# Sheet1.net
KiCad netlist of a schematic drawn in Altium Designer
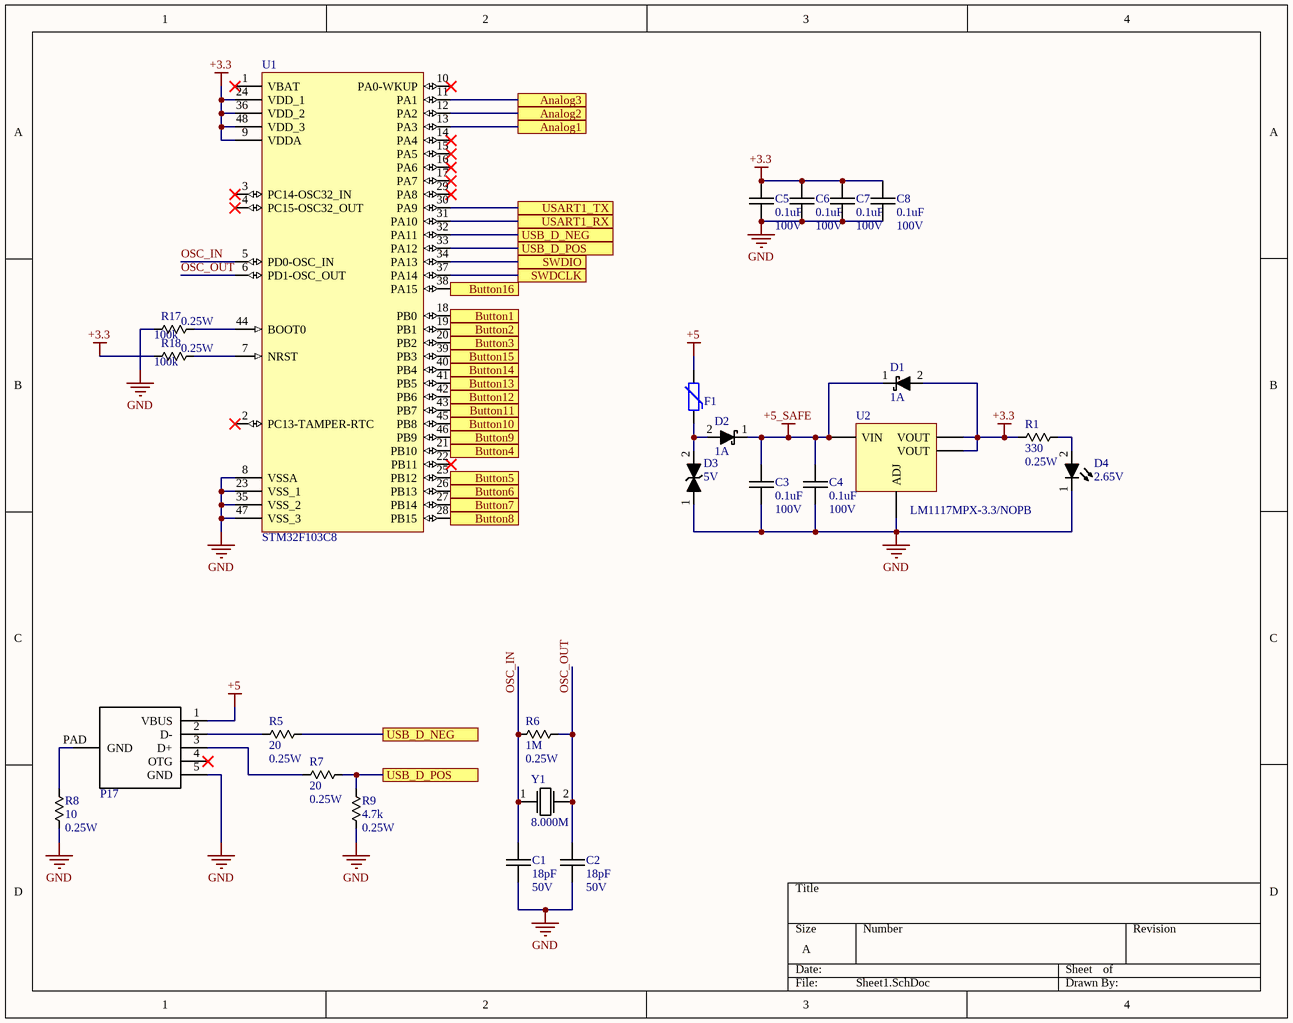
[diagram p0: Sheet1.SchDoc]

(export (version "E")
  (design (tool "Eeschema 10.0.6"))
  (components
    (comp (ref "C1")
      (value "cap_single_np")
      (footprint "chip_0603")
      (description "CAP, 18pF, ±2%, 50V, C0G, 0603")
      (fields
        (field (name "TOLERANCE") "±2%")
        (field (name "CAPACITANCE") "18pF")
        (field (name "VOLTAGE RATING") "50V")
        (field (name "PART NUMBER") "CAP-00409")
      )
      (libsource (lib "Capacitors") (part "cap_single_np"))
    )
    (comp (ref "C2")
      (value "cap_single_np")
      (footprint "chip_0603")
      (description "CAP, 18pF, ±2%, 50V, C0G, 0603")
      (fields
        (field (name "TOLERANCE") "±2%")
        (field (name "CAPACITANCE") "18pF")
        (field (name "VOLTAGE RATING") "50V")
        (field (name "PART NUMBER") "CAP-00409")
      )
      (libsource (lib "Capacitors") (part "cap_single_np"))
    )
    (comp (ref "C3")
      (value "cap_single_np")
      (footprint "chip_0603")
      (description "CAP, 0.1uF, ±10%, 100V, X7R, 0603")
      (fields
        (field (name "TOLERANCE") "±10%")
        (field (name "CAPACITANCE") "0.1uF")
        (field (name "VOLTAGE RATING") "100V")
        (field (name "PART NUMBER") "CAP-00477")
      )
      (libsource (lib "Capacitors") (part "cap_single_np"))
    )
    (comp (ref "C4")
      (value "cap_single_np")
      (footprint "chip_0603")
      (description "CAP, 0.1uF, ±10%, 100V, X7R, 0603")
      (fields
        (field (name "TOLERANCE") "±10%")
        (field (name "CAPACITANCE") "0.1uF")
        (field (name "VOLTAGE RATING") "100V")
        (field (name "PART NUMBER") "CAP-00477")
      )
      (libsource (lib "Capacitors") (part "cap_single_np"))
    )
    (comp (ref "C5")
      (value "cap_single_np")
      (footprint "chip_0603")
      (description "CAP, 0.1uF, ±10%, 100V, X7R, 0603")
      (fields
        (field (name "TOLERANCE") "±10%")
        (field (name "CAPACITANCE") "0.1uF")
        (field (name "VOLTAGE RATING") "100V")
        (field (name "PART NUMBER") "CAP-00477")
      )
      (libsource (lib "Capacitors") (part "cap_single_np"))
    )
    (comp (ref "C6")
      (value "cap_single_np")
      (footprint "chip_0603")
      (description "CAP, 0.1uF, ±10%, 100V, X7R, 0603")
      (fields
        (field (name "TOLERANCE") "±10%")
        (field (name "CAPACITANCE") "0.1uF")
        (field (name "VOLTAGE RATING") "100V")
        (field (name "PART NUMBER") "CAP-00477")
      )
      (libsource (lib "Capacitors") (part "cap_single_np"))
    )
    (comp (ref "C7")
      (value "cap_single_np")
      (footprint "chip_0603")
      (description "CAP, 0.1uF, ±10%, 100V, X7R, 0603")
      (fields
        (field (name "TOLERANCE") "±10%")
        (field (name "CAPACITANCE") "0.1uF")
        (field (name "VOLTAGE RATING") "100V")
        (field (name "PART NUMBER") "CAP-00477")
      )
      (libsource (lib "Capacitors") (part "cap_single_np"))
    )
    (comp (ref "C8")
      (value "cap_single_np")
      (footprint "chip_0603")
      (description "CAP, 0.1uF, ±10%, 100V, X7R, 0603")
      (fields
        (field (name "TOLERANCE") "±10%")
        (field (name "CAPACITANCE") "0.1uF")
        (field (name "VOLTAGE RATING") "100V")
        (field (name "PART NUMBER") "CAP-00477")
      )
      (libsource (lib "Capacitors") (part "cap_single_np"))
    )
    (comp (ref "D1")
      (value "diode_2")
      (footprint "sod123_0")
      (description "Dio Shtky, 1A, 0.55V, 40V, SOD-123")
      (fields
        (field (name "CURRENT RATING") "1A")
        (field (name "PART NUMBER") "DIO-00001")
        (field (name "MANUFACTURER") "ON Semi")
      )
      (libsource (lib "Diodes") (part "diode_2"))
    )
    (comp (ref "D2")
      (value "diode_2")
      (footprint "sod123_0")
      (description "Dio Shtky, 1A, 0.55V, 40V, SOD-123")
      (fields
        (field (name "CURRENT RATING") "1A")
        (field (name "PART NUMBER") "DIO-00001")
        (field (name "MANUFACTURER") "ON Semi")
      )
      (libsource (lib "Diodes") (part "diode_2"))
    )
    (comp (ref "D3")
      (value "diode_5")
      (footprint "sod323_0")
      (description "TVS, 5V, 500W")
      (fields
        (field (name "REVERSE BREAKDOWN VOLTAGE") "5V")
        (field (name "PART NUMBER") "DIO-00037")
        (field (name "MANUFACTURER") "ST")
      )
      (libsource (lib "Diodes") (part "diode_5"))
    )
    (comp (ref "D4")
      (value "diode_4")
      (footprint "chip_0603")
      (description "LED, Green, 0603, Low current, HELI2 Series")
      (fields
        (field (name "FORWARD VOLTAGE") "2.65V")
        (field (name "PART NUMBER") "DIO-00050")
        (field (name "MANUFACTURER") "Kingbright")
      )
      (libsource (lib "Diodes") (part "diode_4"))
    )
    (comp (ref "F1")
      (value "PTC_0")
      (footprint "chip_1206")
      (description "PTC Resettable fuse, 6V, 500mA, 1206")
      (fields (field (name "PART NUMBER") "MISC-00008") (field (name "MANUFACTURER") "Eaton"))
      (libsource (lib "Misc") (part "PTC_0"))
    )
    (comp (ref "P17")
      (value "usb_micro_b")
      (footprint "10118192")
      (description "USB Micro B Type Receptacle")
      (fields (field (name "PART NUMBER") "CONN-00011") (field (name "MANUFACTURER") "Amphenol"))
      (libsource (lib "Connectors") (part "usb_micro_b"))
    )
    (comp (ref "R1")
      (value "res_single")
      (footprint "chip_0603")
      (description "RES SMD 330 OHM 1% 1/4W 0603")
      (fields
        (field (name "TOLERANCE") "1%")
        (field (name "RESISTANCE") "330")
        (field (name "POWER RATING") "0.25W")
        (field (name "PART NUMBER") "RES-00221")
      )
      (libsource (lib "Resistors") (part "res_single"))
    )
    (comp (ref "R5")
      (value "res_single")
      (footprint "chip_0603")
      (description "RES SMD 20 OHM 1% 1/4W 0603")
      (fields
        (field (name "TOLERANCE") "1%")
        (field (name "RESISTANCE") "20")
        (field (name "POWER RATING") "0.25W")
        (field (name "PART NUMBER") "RES-00129")
      )
      (libsource (lib "Resistors") (part "res_single"))
    )
    (comp (ref "R6")
      (value "res_single")
      (footprint "chip_0603")
      (description "RES SMD 1M OHM 1% 1/4W 0603")
      (fields
        (field (name "TOLERANCE") "1%")
        (field (name "RESISTANCE") "1M")
        (field (name "POWER RATING") "0.25W")
        (field (name "PART NUMBER") "RES-00362")
      )
      (libsource (lib "Resistors") (part "res_single"))
    )
    (comp (ref "R7")
      (value "res_single")
      (footprint "chip_0603")
      (description "RES SMD 20 OHM 1% 1/4W 0603")
      (fields
        (field (name "TOLERANCE") "1%")
        (field (name "RESISTANCE") "20")
        (field (name "POWER RATING") "0.25W")
        (field (name "PART NUMBER") "RES-00129")
      )
      (libsource (lib "Resistors") (part "res_single"))
    )
    (comp (ref "R8")
      (value "res_single")
      (footprint "chip_0603")
      (description "RES SMD 10 OHM 1% 1/4W 0603")
      (fields
        (field (name "TOLERANCE") "1%")
        (field (name "RESISTANCE") "10")
        (field (name "POWER RATING") "0.25W")
        (field (name "PART NUMBER") "RES-00116")
      )
      (libsource (lib "Resistors") (part "res_single"))
    )
    (comp (ref "R9")
      (value "res_single")
      (footprint "chip_0603")
      (description "RES SMD 4.7K OHM 1% 1/4W 0603")
      (fields
        (field (name "TOLERANCE") "1%")
        (field (name "RESISTANCE") "4.7k")
        (field (name "POWER RATING") "0.25W")
        (field (name "PART NUMBER") "RES-00470")
      )
      (libsource (lib "Resistors") (part "res_single"))
    )
    (comp (ref "R17")
      (value "res_single")
      (footprint "chip_0603")
      (description "RES SMD 100K OHM 1% 1/4W 0603")
      (fields
        (field (name "TOLERANCE") "1%")
        (field (name "RESISTANCE") "100k")
        (field (name "POWER RATING") "0.25W")
        (field (name "PART NUMBER") "RES-00301")
      )
      (libsource (lib "Resistors") (part "res_single"))
    )
    (comp (ref "R18")
      (value "res_single")
      (footprint "chip_0603")
      (description "RES SMD 100K OHM 1% 1/4W 0603")
      (fields
        (field (name "TOLERANCE") "1%")
        (field (name "RESISTANCE") "100k")
        (field (name "POWER RATING") "0.25W")
        (field (name "PART NUMBER") "RES-00301")
      )
      (libsource (lib "Resistors") (part "res_single"))
    )
    (comp (ref "U1")
      (value "STM32F103C8")
      (footprint "LQFP48_0")
      (description "STM32 M3, LQFP-48")
      (fields (field (name "PART NUMBER") "UCTRL-00008") (field (name "MANUFACTURER") "ST"))
      (libsource (lib "Microcontrollers") (part "STM32F103C8"))
    )
    (comp (ref "U2")
      (value "LM1117")
      (footprint "sot-223-4")
      (description "REG, Linear, Fixed 3V3, 800mA, SOT-223")
      (fields
        (field (name "MANUFACTURER PN") "LM1117MPX-3.3/NOPB")
        (field (name "PART NUMBER") "PWREG-00018")
        (field (name "MANUFACTURER") "TI")
      )
      (libsource (lib "Power Reg") (part "LM1117"))
    )
    (comp (ref "Y1")
      (value "osc_xtal_2p_0")
      (footprint "ABLS_AT49_OSC")
      (description "XTAL, 8MHz, 18pF, 20ppm")
      (fields
        (field (name "TOLERANCE") "20ppm")
        (field (name "FREQUENCY") "8.000M")
        (field (name "PART NUMBER") "OSC-00002")
      )
      (libsource (lib "Oscillators") (part "osc_xtal_2p_0"))
    )
  )
  (nets
    (net (code "1") (name "+3.3") (class "Default")
      (node (ref "C5") (pin "1") (pinfunction "1_1") (pintype "passive"))
      (node (ref "C6") (pin "1") (pinfunction "1_1") (pintype "passive"))
      (node (ref "C7") (pin "1") (pinfunction "1_1") (pintype "passive"))
      (node (ref "C8") (pin "1") (pinfunction "1_1") (pintype "passive"))
      (node (ref "D1") (pin "2") (pinfunction "2_2") (pintype "passive"))
      (node (ref "R1") (pin "1") (pinfunction "1_1") (pintype "passive"))
      (node (ref "R18") (pin "2") (pinfunction "2_2") (pintype "passive"))
      (node (ref "U1") (pin "24") (pinfunction "VDD_1_24") (pintype "power_in"))
      (node (ref "U1") (pin "36") (pinfunction "VDD_2_36") (pintype "power_in"))
      (node (ref "U1") (pin "48") (pinfunction "VDD_3_48") (pintype "power_in"))
      (node (ref "U1") (pin "9") (pinfunction "VDDA_9") (pintype "power_in"))
      (node (ref "U2") (pin "2") (pinfunction "VOUT_2") (pintype "passive"))
      (node (ref "U2") (pin "4") (pinfunction "VOUT_4") (pintype "passive"))
    )
    (net (code "2") (name "+5") (class "Default")
      (node (ref "F1") (pin "2") (pinfunction "2_2") (pintype "passive"))
      (node (ref "P17") (pin "1") (pinfunction "VBUS_1") (pintype "passive"))
    )
    (net (code "3") (name "+5_SAFE") (class "Default")
      (node (ref "C3") (pin "1") (pinfunction "1_1") (pintype "passive"))
      (node (ref "C4") (pin "1") (pinfunction "1_1") (pintype "passive"))
      (node (ref "D1") (pin "1") (pinfunction "1_1") (pintype "passive"))
      (node (ref "D2") (pin "1") (pinfunction "1_1") (pintype "passive"))
      (node (ref "U2") (pin "3") (pinfunction "VIN_3") (pintype "passive"))
    )
    (net (code "4") (name "/Analog1") (class "Default")
      (node (ref "U1") (pin "13") (pinfunction "PA3_13") (pintype "bidirectional"))
    )
    (net (code "5") (name "/Analog2") (class "Default")
      (node (ref "U1") (pin "12") (pinfunction "PA2_12") (pintype "bidirectional"))
    )
    (net (code "6") (name "/Analog3") (class "Default")
      (node (ref "U1") (pin "11") (pinfunction "PA1_11") (pintype "bidirectional"))
    )
    (net (code "7") (name "/Button1") (class "Default")
      (node (ref "U1") (pin "18") (pinfunction "PB0_18") (pintype "bidirectional"))
    )
    (net (code "8") (name "/Button2") (class "Default")
      (node (ref "U1") (pin "19") (pinfunction "PB1_19") (pintype "bidirectional"))
    )
    (net (code "9") (name "/Button3") (class "Default")
      (node (ref "U1") (pin "20") (pinfunction "PB2_20") (pintype "bidirectional"))
    )
    (net (code "10") (name "/Button4") (class "Default")
      (node (ref "U1") (pin "21") (pinfunction "PB10_21") (pintype "bidirectional"))
    )
    (net (code "11") (name "/Button5") (class "Default")
      (node (ref "U1") (pin "25") (pinfunction "PB12_25") (pintype "bidirectional"))
    )
    (net (code "12") (name "/Button6") (class "Default")
      (node (ref "U1") (pin "26") (pinfunction "PB13_26") (pintype "bidirectional"))
    )
    (net (code "13") (name "/Button7") (class "Default")
      (node (ref "U1") (pin "27") (pinfunction "PB14_27") (pintype "bidirectional"))
    )
    (net (code "14") (name "/Button8") (class "Default")
      (node (ref "U1") (pin "28") (pinfunction "PB15_28") (pintype "bidirectional"))
    )
    (net (code "15") (name "/Button9") (class "Default")
      (node (ref "U1") (pin "46") (pinfunction "PB9_46") (pintype "bidirectional"))
    )
    (net (code "16") (name "/Button10") (class "Default")
      (node (ref "U1") (pin "45") (pinfunction "PB8_45") (pintype "bidirectional"))
    )
    (net (code "17") (name "/Button11") (class "Default")
      (node (ref "U1") (pin "43") (pinfunction "PB7_43") (pintype "bidirectional"))
    )
    (net (code "18") (name "/Button12") (class "Default")
      (node (ref "U1") (pin "42") (pinfunction "PB6_42") (pintype "bidirectional"))
    )
    (net (code "19") (name "/Button13") (class "Default")
      (node (ref "U1") (pin "41") (pinfunction "PB5_41") (pintype "bidirectional"))
    )
    (net (code "20") (name "/Button14") (class "Default")
      (node (ref "U1") (pin "40") (pinfunction "PB4_40") (pintype "bidirectional"))
    )
    (net (code "21") (name "/Button15") (class "Default")
      (node (ref "U1") (pin "39") (pinfunction "PB3_39") (pintype "bidirectional"))
    )
    (net (code "22") (name "/Button16") (class "Default")
      (node (ref "U1") (pin "38") (pinfunction "PA15_38") (pintype "bidirectional"))
    )
    (net (code "23") (name "/OSC_IN") (class "Default")
      (node (ref "C1") (pin "1") (pinfunction "1_1") (pintype "passive"))
      (node (ref "R6") (pin "1") (pinfunction "1_1") (pintype "passive"))
      (node (ref "U1") (pin "5") (pinfunction "PD0-OSC_IN_5") (pintype "bidirectional"))
      (node (ref "Y1") (pin "1") (pinfunction "20_1") (pintype "passive"))
    )
    (net (code "24") (name "/OSC_OUT") (class "Default")
      (node (ref "C2") (pin "2") (pinfunction "2_2") (pintype "passive"))
      (node (ref "R6") (pin "2") (pinfunction "2_2") (pintype "passive"))
      (node (ref "U1") (pin "6") (pinfunction "PD1-OSC_OUT_6") (pintype "bidirectional"))
      (node (ref "Y1") (pin "2") (pinfunction "20_2") (pintype "passive"))
    )
    (net (code "25") (name "/SWDCLK") (class "Default")
      (node (ref "U1") (pin "37") (pinfunction "PA14_37") (pintype "bidirectional"))
    )
    (net (code "26") (name "/SWDIO") (class "Default")
      (node (ref "U1") (pin "34") (pinfunction "PA13_34") (pintype "bidirectional"))
    )
    (net (code "27") (name "/USART1_RX") (class "Default")
      (node (ref "U1") (pin "31") (pinfunction "PA10_31") (pintype "bidirectional"))
    )
    (net (code "28") (name "/USART1_TX") (class "Default")
      (node (ref "U1") (pin "30") (pinfunction "PA9_30") (pintype "bidirectional"))
    )
    (net (code "29") (name "/USB_D_NEG") (class "Default")
      (node (ref "R5") (pin "2") (pinfunction "2_2") (pintype "passive"))
      (node (ref "U1") (pin "32") (pinfunction "PA11_32") (pintype "bidirectional"))
    )
    (net (code "30") (name "/USB_D_POS") (class "Default")
      (node (ref "R7") (pin "2") (pinfunction "2_2") (pintype "passive"))
      (node (ref "R9") (pin "1") (pinfunction "1_1") (pintype "passive"))
      (node (ref "U1") (pin "33") (pinfunction "PA12_33") (pintype "bidirectional"))
    )
    (net (code "31") (name "GND") (class "Default")
      (node (ref "C1") (pin "2") (pinfunction "2_2") (pintype "passive"))
      (node (ref "C2") (pin "1") (pinfunction "1_1") (pintype "passive"))
      (node (ref "C3") (pin "2") (pinfunction "2_2") (pintype "passive"))
      (node (ref "C4") (pin "2") (pinfunction "2_2") (pintype "passive"))
      (node (ref "C5") (pin "2") (pinfunction "2_2") (pintype "passive"))
      (node (ref "C6") (pin "2") (pinfunction "2_2") (pintype "passive"))
      (node (ref "C7") (pin "2") (pinfunction "2_2") (pintype "passive"))
      (node (ref "C8") (pin "2") (pinfunction "2_2") (pintype "passive"))
      (node (ref "D3") (pin "1") (pinfunction "1_1") (pintype "passive"))
      (node (ref "D4") (pin "1") (pinfunction "1_1") (pintype "passive"))
      (node (ref "P17") (pin "5") (pinfunction "GND_5") (pintype "passive"))
      (node (ref "R17") (pin "2") (pinfunction "2_2") (pintype "passive"))
      (node (ref "R8") (pin "2") (pinfunction "2_2") (pintype "passive"))
      (node (ref "R9") (pin "2") (pinfunction "2_2") (pintype "passive"))
      (node (ref "U1") (pin "23") (pinfunction "VSS_1_23") (pintype "power_in"))
      (node (ref "U1") (pin "35") (pinfunction "VSS_2_35") (pintype "power_in"))
      (node (ref "U1") (pin "47") (pinfunction "VSS_3_47") (pintype "power_in"))
      (node (ref "U1") (pin "8") (pinfunction "VSSA_8") (pintype "power_in"))
      (node (ref "U2") (pin "1") (pinfunction "ADJ_1") (pintype "passive"))
    )
    (net (code "32") (name "Net-(D2-Pad2)") (class "Default")
      (node (ref "D2") (pin "2") (pinfunction "2_2") (pintype "passive"))
      (node (ref "D3") (pin "2") (pinfunction "2_2") (pintype "passive"))
      (node (ref "F1") (pin "1") (pinfunction "1_1") (pintype "passive"))
    )
    (net (code "33") (name "Net-(D4-Pad2)") (class "Default")
      (node (ref "D4") (pin "2") (pinfunction "2_2") (pintype "passive"))
      (node (ref "R1") (pin "2") (pinfunction "2_2") (pintype "passive"))
    )
    (net (code "34") (name "Net-(P17-D+)") (class "Default")
      (node (ref "P17") (pin "3") (pinfunction "D+_3") (pintype "passive"))
      (node (ref "R7") (pin "1") (pinfunction "1_1") (pintype "passive"))
    )
    (net (code "35") (name "Net-(P17-D-)") (class "Default")
      (node (ref "P17") (pin "2") (pinfunction "D-_2") (pintype "passive"))
      (node (ref "R5") (pin "1") (pinfunction "1_1") (pintype "passive"))
    )
    (net (code "36") (name "Net-(P17-GND-PadPAD)") (class "Default")
      (node (ref "P17") (pin "PAD") (pinfunction "GND_PAD") (pintype "passive"))
      (node (ref "R8") (pin "1") (pinfunction "1_1") (pintype "passive"))
    )
    (net (code "37") (name "Net-(U1-BOOT0)") (class "Default")
      (node (ref "R17") (pin "1") (pinfunction "1_1") (pintype "passive"))
      (node (ref "U1") (pin "44") (pinfunction "BOOT0_44") (pintype "input"))
    )
    (net (code "38") (name "Net-(U1-NRST)") (class "Default")
      (node (ref "R18") (pin "1") (pinfunction "1_1") (pintype "passive"))
      (node (ref "U1") (pin "7") (pinfunction "NRST_7") (pintype "input"))
    )
    (net (code "39") (name "unconnected-(P17-OTG-Pad4)") (class "Default")
      (node (ref "P17") (pin "4") (pinfunction "OTG_4") (pintype "passive+no_connect"))
    )
    (net (code "40") (name "unconnected-(U1-PA0-WKUP-Pad10)") (class "Default")
      (node (ref "U1") (pin "10") (pinfunction "PA0-WKUP_10") (pintype "bidirectional+no_connect"))
    )
    (net (code "41") (name "unconnected-(U1-PA4-Pad14)") (class "Default")
      (node (ref "U1") (pin "14") (pinfunction "PA4_14") (pintype "bidirectional+no_connect"))
    )
    (net (code "42") (name "unconnected-(U1-PA5-Pad15)") (class "Default")
      (node (ref "U1") (pin "15") (pinfunction "PA5_15") (pintype "bidirectional+no_connect"))
    )
    (net (code "43") (name "unconnected-(U1-PA6-Pad16)") (class "Default")
      (node (ref "U1") (pin "16") (pinfunction "PA6_16") (pintype "bidirectional+no_connect"))
    )
    (net (code "44") (name "unconnected-(U1-PA7-Pad17)") (class "Default")
      (node (ref "U1") (pin "17") (pinfunction "PA7_17") (pintype "bidirectional+no_connect"))
    )
    (net (code "45") (name "unconnected-(U1-PA8-Pad29)") (class "Default")
      (node (ref "U1") (pin "29") (pinfunction "PA8_29") (pintype "bidirectional+no_connect"))
    )
    (net (code "46") (name "unconnected-(U1-PB11-Pad22)") (class "Default")
      (node (ref "U1") (pin "22") (pinfunction "PB11_22") (pintype "bidirectional+no_connect"))
    )
    (net (code "47") (name "unconnected-(U1-PC13-TAMPER-RTC-Pad2)") (class "Default")
      (node (ref "U1") (pin "2") (pinfunction "PC13-TAMPER-RTC_2") (pintype "bidirectional+no_connect"))
    )
    (net (code "48") (name "unconnected-(U1-PC14-OSC32_IN-Pad3)") (class "Default")
      (node (ref "U1") (pin "3") (pinfunction "PC14-OSC32_IN_3") (pintype "bidirectional+no_connect"))
    )
    (net (code "49") (name "unconnected-(U1-PC15-OSC32_OUT-Pad4)") (class "Default")
      (node (ref "U1") (pin "4") (pinfunction "PC15-OSC32_OUT_4") (pintype "bidirectional+no_connect"))
    )
    (net (code "50") (name "unconnected-(U1-VBAT-Pad1)") (class "Default")
      (node (ref "U1") (pin "1") (pinfunction "VBAT_1") (pintype "passive+no_connect"))
    )
  )
)
